# rev0_1.net
KiCad netlist of a schematic drawn in EAGLE
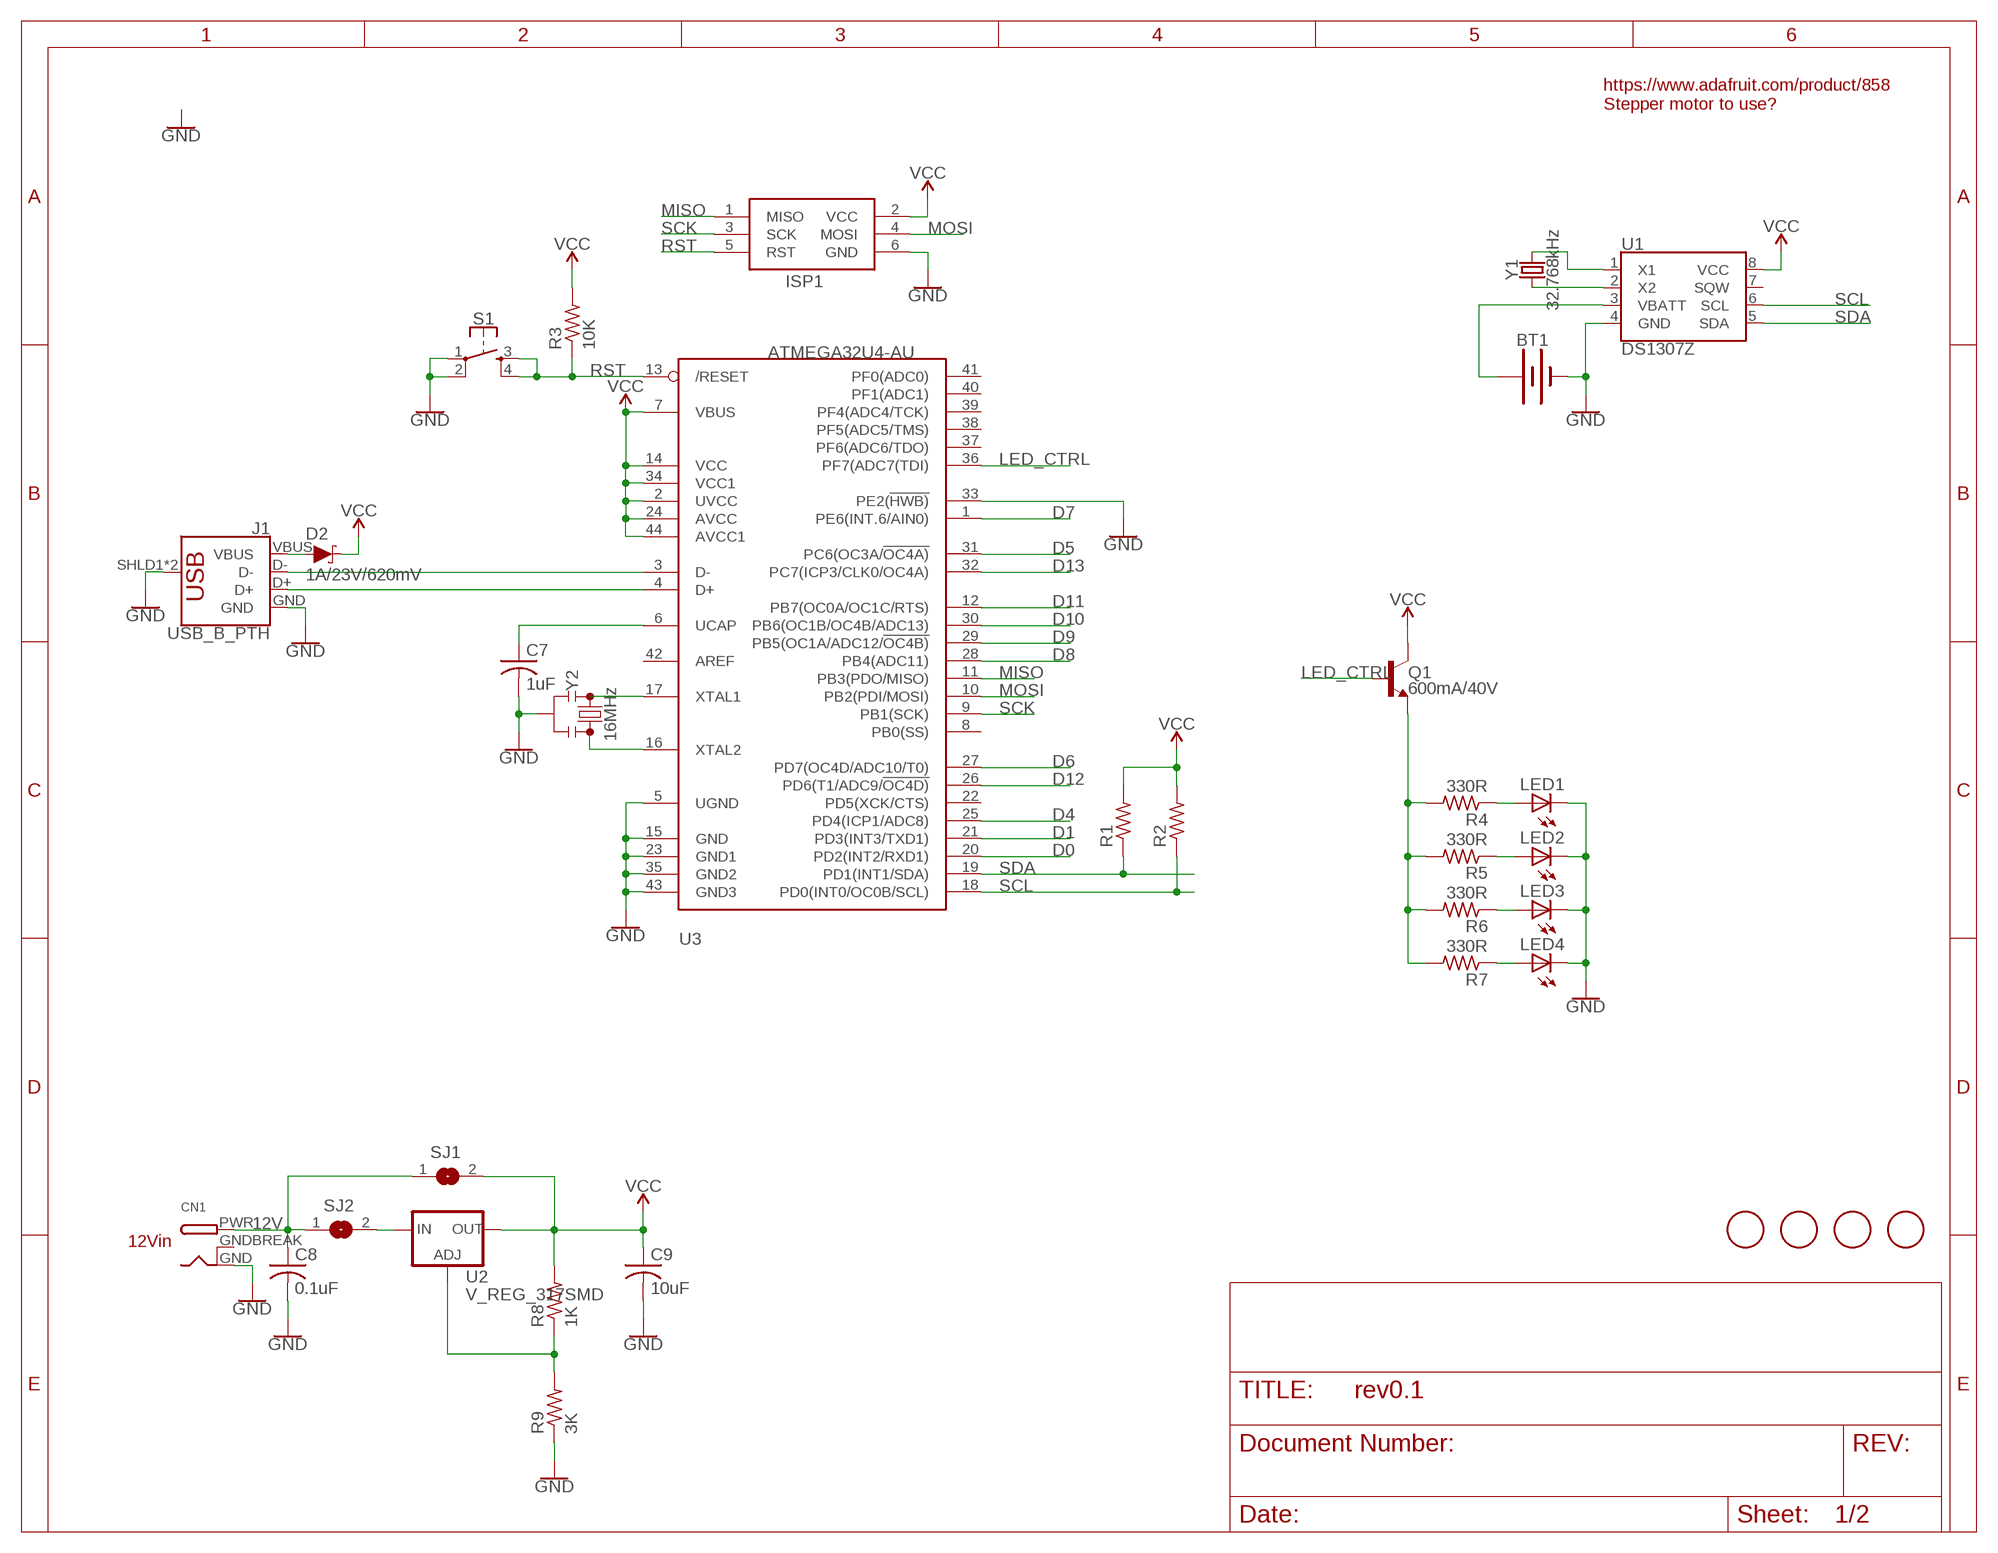
[diagram p0: schematic, sheet 1]
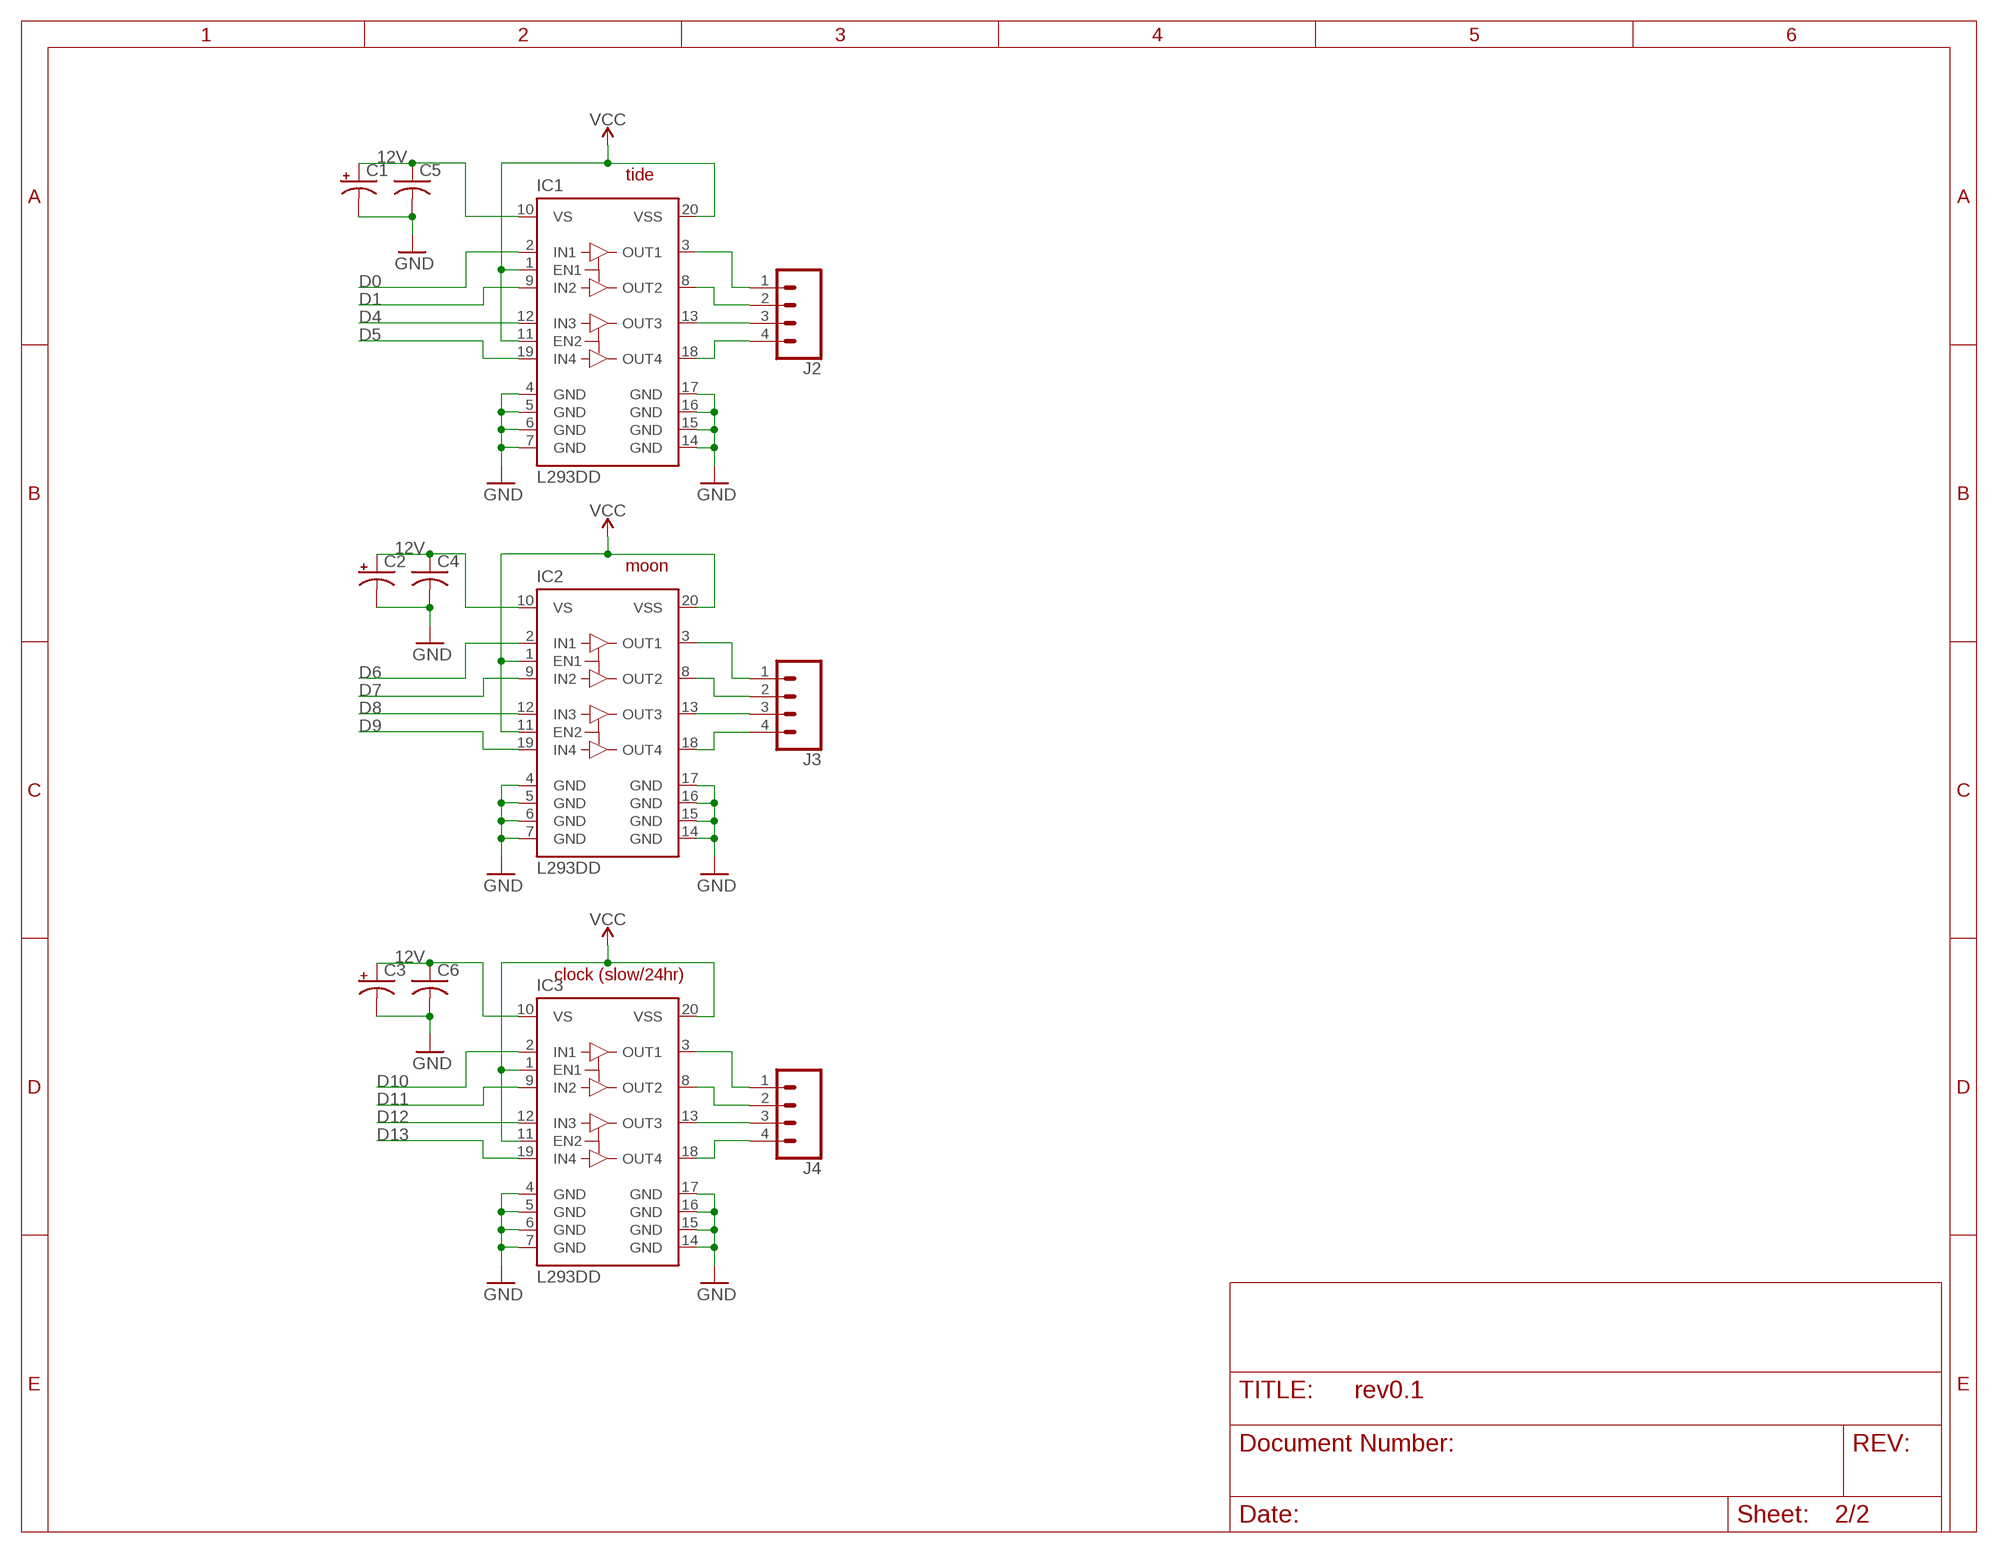
[diagram p1: schematic, sheet 2]

(export (version "E")
  (design (tool "Eeschema 10.0.6"))
  (components
    (comp (ref "C1")
      (value "CPOL-USD")
      (footprint "eagle-import:PANASONIC_D")
      (libsource (lib "eagle-import") (part "CPOL-USD"))
    )
    (comp (ref "C2")
      (value "CPOL-USD")
      (footprint "eagle-import:PANASONIC_D")
      (libsource (lib "eagle-import") (part "CPOL-USD"))
    )
    (comp (ref "C3")
      (value "CPOL-USD")
      (footprint "eagle-import:PANASONIC_D")
      (libsource (lib "eagle-import") (part "CPOL-USD"))
    )
    (comp (ref "C4")
      (value "C-USC0805")
      (footprint "eagle-import:C0805")
      (libsource (lib "eagle-import") (part "C-USC0805"))
    )
    (comp (ref "C5")
      (value "C-USC0805")
      (footprint "eagle-import:C0805")
      (libsource (lib "eagle-import") (part "C-USC0805"))
    )
    (comp (ref "C6")
      (value "C-USC0805")
      (footprint "eagle-import:C0805")
      (libsource (lib "eagle-import") (part "C-USC0805"))
    )
    (comp (ref "IC1")
      (value "L293DD")
      (footprint "eagle-import:SO20")
      (libsource (lib "eagle-import") (part "L293DD"))
    )
    (comp (ref "IC2")
      (value "L293DD")
      (footprint "eagle-import:SO20")
      (libsource (lib "eagle-import") (part "L293DD"))
    )
    (comp (ref "IC3")
      (value "L293DD")
      (footprint "eagle-import:SO20")
      (libsource (lib "eagle-import") (part "L293DD"))
    )
    (comp (ref "J2")
      (value "CONN_04LOCK")
      (footprint "eagle-import:1X04_LOCK")
      (libsource (lib "eagle-import") (part "CONN_04LOCK"))
    )
    (comp (ref "J3")
      (value "CONN_04LOCK")
      (footprint "eagle-import:1X04_LOCK")
      (libsource (lib "eagle-import") (part "CONN_04LOCK"))
    )
    (comp (ref "J4")
      (value "CONN_04LOCK")
      (footprint "eagle-import:1X04_LOCK")
      (libsource (lib "eagle-import") (part "CONN_04LOCK"))
    )
    (comp (ref "BT1")
      (value "BATTERY-12MM_SMD")
      (footprint "eagle-import:BATTCON_12MM")
      (libsource (lib "eagle-import") (part "BATTERY-12MM_SMD"))
    )
    (comp (ref "C7")
      (value "1uF")
      (footprint "eagle-import:C0805")
      (libsource (lib "eagle-import") (part "C-USC0805"))
    )
    (comp (ref "C8")
      (value "0.1uF")
      (footprint "eagle-import:C0805")
      (libsource (lib "eagle-import") (part "C-USC0805"))
    )
    (comp (ref "C9")
      (value "10uF")
      (footprint "eagle-import:C0805")
      (libsource (lib "eagle-import") (part "C-USC0805"))
    )
    (comp (ref "CN1")
      (value "DCBARRELPTH")
      (footprint "eagle-import:DCJACK_2MM_PTH")
      (libsource (lib "eagle-import") (part "DCBARRELPTH"))
    )
    (comp (ref "D2")
      (value "1A/23V/620mV")
      (footprint "eagle-import:SOD-323")
      (libsource (lib "eagle-import") (part "DIODE-SCHOTTKY-BAT20J"))
    )
    (comp (ref "ISP1")
      (value "AVRISP-6")
      (footprint "eagle-import:AVRISP")
      (libsource (lib "eagle-import") (part "AVRISP-6"))
    )
    (comp (ref "J1")
      (value "USB_B_PTH")
      (footprint "eagle-import:USB-B-PTH")
      (libsource (lib "eagle-import") (part "USB_B_PTH"))
    )
    (comp (ref "LED1")
      (value "LEDCHIPLED_0805")
      (footprint "eagle-import:CHIPLED_0805")
      (libsource (lib "eagle-import") (part "LEDCHIPLED_0805"))
    )
    (comp (ref "LED2")
      (value "LEDCHIPLED_0805")
      (footprint "eagle-import:CHIPLED_0805")
      (libsource (lib "eagle-import") (part "LEDCHIPLED_0805"))
    )
    (comp (ref "LED3")
      (value "LEDCHIPLED_0805")
      (footprint "eagle-import:CHIPLED_0805")
      (libsource (lib "eagle-import") (part "LEDCHIPLED_0805"))
    )
    (comp (ref "LED4")
      (value "LEDCHIPLED_0805")
      (footprint "eagle-import:CHIPLED_0805")
      (libsource (lib "eagle-import") (part "LEDCHIPLED_0805"))
    )
    (comp (ref "Q1")
      (value "600mA/40V")
      (footprint "eagle-import:SOT23-3")
      (libsource (lib "eagle-import") (part "TRANS_NPN-MMBT2222AL"))
    )
    (comp (ref "R1")
      (value "R-US_R0805")
      (footprint "eagle-import:R0805")
      (libsource (lib "eagle-import") (part "R-US_R0805"))
    )
    (comp (ref "R2")
      (value "R-US_R0805")
      (footprint "eagle-import:R0805")
      (libsource (lib "eagle-import") (part "R-US_R0805"))
    )
    (comp (ref "R3")
      (value "10K")
      (footprint "eagle-import:R0805")
      (libsource (lib "eagle-import") (part "R-US_R0805"))
    )
    (comp (ref "R4")
      (value "330R")
      (footprint "eagle-import:R0805")
      (libsource (lib "eagle-import") (part "R-US_R0805"))
    )
    (comp (ref "R5")
      (value "330R")
      (footprint "eagle-import:R0805")
      (libsource (lib "eagle-import") (part "R-US_R0805"))
    )
    (comp (ref "R6")
      (value "330R")
      (footprint "eagle-import:R0805")
      (libsource (lib "eagle-import") (part "R-US_R0805"))
    )
    (comp (ref "R7")
      (value "330R")
      (footprint "eagle-import:R0805")
      (libsource (lib "eagle-import") (part "R-US_R0805"))
    )
    (comp (ref "R8")
      (value "1K")
      (footprint "eagle-import:R0805")
      (libsource (lib "eagle-import") (part "R-US_R0805"))
    )
    (comp (ref "R9")
      (value "3K")
      (footprint "eagle-import:R0805")
      (libsource (lib "eagle-import") (part "R-US_R0805"))
    )
    (comp (ref "S1")
      (value "MOMENTARY-SWITCH-SPST-2-SMD-5.2MM")
      (footprint "eagle-import:TACTILE_SWITCH_SMD_5.2MM")
      (libsource (lib "eagle-import") (part "MOMENTARY-SWITCH-SPST-2-SMD-5.2MM"))
    )
    (comp (ref "SJ1") (value "SJ") (footprint "eagle-import:SJ") (libsource (lib "eagle-import") (part "SJ")))
    (comp (ref "SJ2") (value "SJ") (footprint "eagle-import:SJ") (libsource (lib "eagle-import") (part "SJ")))
    (comp (ref "U$2")
      (value "FIDUCIAL")
      (footprint "eagle-import:FIDUCIAL_1MM")
      (libsource (lib "eagle-import") (part "FIDUCIAL"))
    )
    (comp (ref "U$3")
      (value "FIDUCIAL")
      (footprint "eagle-import:FIDUCIAL_1MM")
      (libsource (lib "eagle-import") (part "FIDUCIAL"))
    )
    (comp (ref "U$4")
      (value "FIDUCIAL")
      (footprint "eagle-import:FIDUCIAL_1MM")
      (libsource (lib "eagle-import") (part "FIDUCIAL"))
    )
    (comp (ref "U$5")
      (value "FIDUCIAL")
      (footprint "eagle-import:FIDUCIAL_1MM")
      (libsource (lib "eagle-import") (part "FIDUCIAL"))
    )
    (comp (ref "U1")
      (value "DS1307Z")
      (footprint "eagle-import:SO08-0.15")
      (libsource (lib "eagle-import") (part "DS1307Z"))
    )
    (comp (ref "U2")
      (value "V_REG_317SMD")
      (footprint "eagle-import:SOT223")
      (libsource (lib "eagle-import") (part "V_REG_317SMD"))
    )
    (comp (ref "U3")
      (value "ATMEGA32U4-AU")
      (footprint "eagle-import:TQFP44")
      (libsource (lib "eagle-import") (part "ATMEGA32U4-AU"))
    )
    (comp (ref "Y1")
      (value "32.768kHz")
      (footprint "eagle-import:CRYSTAL-PTH-2X6-CYL-KIT")
      (libsource (lib "eagle-import") (part "CRYSTAL-32.768KHZPTH-2X6-KIT"))
    )
    (comp (ref "Y2")
      (value "16MHz")
      (footprint "eagle-import:RESONATOR-SMD-3.2X1.3")
      (libsource (lib "eagle-import") (part "RESONATOR-16MHZSMD_3.2X1.3"))
    )
  )
  (nets
    (net (code "1") (name "12V") (class "Default")
      (node (ref "C1") (pin "+") (pinfunction "+_+") (pintype "passive"))
      (node (ref "C2") (pin "+") (pinfunction "+_+") (pintype "passive"))
      (node (ref "C3") (pin "+") (pinfunction "+_+") (pintype "passive"))
      (node (ref "C4") (pin "1") (pinfunction "1_1") (pintype "passive"))
      (node (ref "C5") (pin "1") (pinfunction "1_1") (pintype "passive"))
      (node (ref "C6") (pin "1") (pinfunction "1_1") (pintype "passive"))
      (node (ref "C8") (pin "1") (pinfunction "1_1") (pintype "passive"))
      (node (ref "CN1") (pin "PWR") (pinfunction "PWR_PWR") (pintype "power_in"))
      (node (ref "IC1") (pin "10") (pinfunction "VS_10") (pintype "power_in"))
      (node (ref "IC2") (pin "10") (pinfunction "VS_10") (pintype "power_in"))
      (node (ref "IC3") (pin "10") (pinfunction "VS_10") (pintype "power_in"))
      (node (ref "SJ1") (pin "1") (pinfunction "1_1") (pintype "passive"))
      (node (ref "SJ2") (pin "1") (pinfunction "1_1") (pintype "passive"))
    )
    (net (code "2") (name "D0") (class "Default")
      (node (ref "IC1") (pin "2") (pinfunction "IN1_2") (pintype "input"))
      (node (ref "U3") (pin "20") (pinfunction "PD2(INT2/RXD1)_20") (pintype "bidirectional"))
    )
    (net (code "3") (name "D1") (class "Default")
      (node (ref "IC1") (pin "9") (pinfunction "IN2_9") (pintype "input"))
      (node (ref "U3") (pin "21") (pinfunction "PD3(INT3/TXD1)_21") (pintype "bidirectional"))
    )
    (net (code "4") (name "D4") (class "Default")
      (node (ref "IC1") (pin "12") (pinfunction "IN3_12") (pintype "input"))
      (node (ref "U3") (pin "25") (pinfunction "PD4(ICP1/ADC8)_25") (pintype "bidirectional"))
    )
    (net (code "5") (name "D5") (class "Default")
      (node (ref "IC1") (pin "19") (pinfunction "IN4_19") (pintype "input"))
      (node (ref "U3") (pin "31") (pinfunction "PC6(OC3A/~{OC4A})_31") (pintype "bidirectional"))
    )
    (net (code "6") (name "D6") (class "Default")
      (node (ref "IC2") (pin "2") (pinfunction "IN1_2") (pintype "input"))
      (node (ref "U3") (pin "27") (pinfunction "PD7(OC4D/ADC10/T0)_27") (pintype "bidirectional"))
    )
    (net (code "7") (name "D7") (class "Default")
      (node (ref "IC2") (pin "9") (pinfunction "IN2_9") (pintype "input"))
      (node (ref "U3") (pin "1") (pinfunction "PE6(INT.6/AIN0)_1") (pintype "bidirectional"))
    )
    (net (code "8") (name "D8") (class "Default")
      (node (ref "IC2") (pin "12") (pinfunction "IN3_12") (pintype "input"))
      (node (ref "U3") (pin "28") (pinfunction "PB4(ADC11)_28") (pintype "bidirectional"))
    )
    (net (code "9") (name "D9") (class "Default")
      (node (ref "IC2") (pin "19") (pinfunction "IN4_19") (pintype "input"))
      (node (ref "U3") (pin "29") (pinfunction "PB5(OC1A/ADC12/~{OC4B})_29") (pintype "bidirectional"))
    )
    (net (code "10") (name "D10") (class "Default")
      (node (ref "IC3") (pin "2") (pinfunction "IN1_2") (pintype "input"))
      (node (ref "U3") (pin "30") (pinfunction "PB6(OC1B/OC4B/ADC13)_30") (pintype "bidirectional"))
    )
    (net (code "11") (name "D11") (class "Default")
      (node (ref "IC3") (pin "9") (pinfunction "IN2_9") (pintype "input"))
      (node (ref "U3") (pin "12") (pinfunction "PB7(OC0A/OC1C/RTS)_12") (pintype "bidirectional"))
    )
    (net (code "12") (name "D12") (class "Default")
      (node (ref "IC3") (pin "12") (pinfunction "IN3_12") (pintype "input"))
      (node (ref "U3") (pin "26") (pinfunction "PD6(T1/ADC9/~{OC4D})_26") (pintype "bidirectional"))
    )
    (net (code "13") (name "D13") (class "Default")
      (node (ref "IC3") (pin "19") (pinfunction "IN4_19") (pintype "input"))
      (node (ref "U3") (pin "32") (pinfunction "PC7(ICP3/CLK0/OC4A)_32") (pintype "bidirectional"))
    )
    (net (code "14") (name "GND") (class "Default")
      (node (ref "BT1") (pin "GND") (pinfunction "-_GND") (pintype "power_in"))
      (node (ref "C1") (pin "-") (pinfunction "-_-") (pintype "passive"))
      (node (ref "C2") (pin "-") (pinfunction "-_-") (pintype "passive"))
      (node (ref "C3") (pin "-") (pinfunction "-_-") (pintype "passive"))
      (node (ref "C4") (pin "2") (pinfunction "2_2") (pintype "passive"))
      (node (ref "C5") (pin "2") (pinfunction "2_2") (pintype "passive"))
      (node (ref "C6") (pin "2") (pinfunction "2_2") (pintype "passive"))
      (node (ref "C7") (pin "2") (pinfunction "2_2") (pintype "passive"))
      (node (ref "C8") (pin "2") (pinfunction "2_2") (pintype "passive"))
      (node (ref "C9") (pin "2") (pinfunction "2_2") (pintype "passive"))
      (node (ref "CN1") (pin "GND") (pinfunction "GND_GND") (pintype "power_in"))
      (node (ref "IC1") (pin "14") (pinfunction "GND_14") (pintype "power_in"))
      (node (ref "IC1") (pin "15") (pinfunction "GND_15") (pintype "power_in"))
      (node (ref "IC1") (pin "16") (pinfunction "GND_16") (pintype "power_in"))
      (node (ref "IC1") (pin "17") (pinfunction "GND_17") (pintype "power_in"))
      (node (ref "IC1") (pin "4") (pinfunction "GND_4") (pintype "power_in"))
      (node (ref "IC1") (pin "5") (pinfunction "GND_5") (pintype "power_in"))
      (node (ref "IC1") (pin "6") (pinfunction "GND_6") (pintype "power_in"))
      (node (ref "IC1") (pin "7") (pinfunction "GND_7") (pintype "power_in"))
      (node (ref "IC2") (pin "14") (pinfunction "GND_14") (pintype "power_in"))
      (node (ref "IC2") (pin "15") (pinfunction "GND_15") (pintype "power_in"))
      (node (ref "IC2") (pin "16") (pinfunction "GND_16") (pintype "power_in"))
      (node (ref "IC2") (pin "17") (pinfunction "GND_17") (pintype "power_in"))
      (node (ref "IC2") (pin "4") (pinfunction "GND_4") (pintype "power_in"))
      (node (ref "IC2") (pin "5") (pinfunction "GND_5") (pintype "power_in"))
      (node (ref "IC2") (pin "6") (pinfunction "GND_6") (pintype "power_in"))
      (node (ref "IC2") (pin "7") (pinfunction "GND_7") (pintype "power_in"))
      (node (ref "IC3") (pin "14") (pinfunction "GND_14") (pintype "power_in"))
      (node (ref "IC3") (pin "15") (pinfunction "GND_15") (pintype "power_in"))
      (node (ref "IC3") (pin "16") (pinfunction "GND_16") (pintype "power_in"))
      (node (ref "IC3") (pin "17") (pinfunction "GND_17") (pintype "power_in"))
      (node (ref "IC3") (pin "4") (pinfunction "GND_4") (pintype "power_in"))
      (node (ref "IC3") (pin "5") (pinfunction "GND_5") (pintype "power_in"))
      (node (ref "IC3") (pin "6") (pinfunction "GND_6") (pintype "power_in"))
      (node (ref "IC3") (pin "7") (pinfunction "GND_7") (pintype "power_in"))
      (node (ref "ISP1") (pin "6") (pinfunction "GND_6") (pintype "power_in"))
      (node (ref "J1") (pin "GND") (pinfunction "GND_GND") (pintype "power_in"))
      (node (ref "J1") (pin "SHLD1") (pinfunction "SHIELD_SHLD1") (pintype "bidirectional"))
      (node (ref "J1") (pin "SHLD2") (pinfunction "SHIELD_SHLD2") (pintype "bidirectional"))
      (node (ref "LED1") (pin "C") (pinfunction "C_C") (pintype "passive"))
      (node (ref "LED2") (pin "C") (pinfunction "C_C") (pintype "passive"))
      (node (ref "LED3") (pin "C") (pinfunction "C_C") (pintype "passive"))
      (node (ref "LED4") (pin "C") (pinfunction "C_C") (pintype "passive"))
      (node (ref "R9") (pin "1") (pinfunction "1_1") (pintype "passive"))
      (node (ref "S1") (pin "1") (pinfunction "1_1") (pintype "passive"))
      (node (ref "S1") (pin "2") (pinfunction "2_2") (pintype "passive"))
      (node (ref "U1") (pin "4") (pinfunction "GND_4") (pintype "bidirectional"))
      (node (ref "U3") (pin "15") (pinfunction "GND_15") (pintype "bidirectional"))
      (node (ref "U3") (pin "23") (pinfunction "GND1_23") (pintype "bidirectional"))
      (node (ref "U3") (pin "33") (pinfunction "PE2(~{HWB})_33") (pintype "bidirectional"))
      (node (ref "U3") (pin "35") (pinfunction "GND2_35") (pintype "bidirectional"))
      (node (ref "U3") (pin "43") (pinfunction "GND3_43") (pintype "bidirectional"))
      (node (ref "U3") (pin "5") (pinfunction "UGND_5") (pintype "bidirectional"))
      (node (ref "Y2") (pin "2") (pinfunction "2_2") (pintype "passive"))
    )
    (net (code "15") (name "GNDBREAK") (class "Default")
      (node (ref "CN1") (pin "GNDBREAK") (pinfunction "GNDBREAK_GNDBREAK") (pintype "power_in"))
    )
    (net (code "16") (name "LED_CTRL") (class "Default")
      (node (ref "Q1") (pin "1") (pinfunction "B_1") (pintype "passive"))
      (node (ref "U3") (pin "36") (pinfunction "PF7(ADC7(TDI)_36") (pintype "bidirectional"))
    )
    (net (code "17") (name "MISO") (class "Default")
      (node (ref "ISP1") (pin "1") (pinfunction "MISO_1") (pintype "input"))
      (node (ref "U3") (pin "11") (pinfunction "PB3(PDO/MISO)_11") (pintype "bidirectional"))
    )
    (net (code "18") (name "MOSI") (class "Default")
      (node (ref "ISP1") (pin "4") (pinfunction "MOSI_4") (pintype "output"))
      (node (ref "U3") (pin "10") (pinfunction "PB2(PDI/MOSI)_10") (pintype "bidirectional"))
    )
    (net (code "19") (name "Net-(BT1-+)") (class "Default")
      (node (ref "BT1") (pin "PWR@1") (pinfunction "+_PWR@1") (pintype "power_in"))
      (node (ref "U1") (pin "3") (pinfunction "VBATT_3") (pintype "bidirectional"))
    )
    (net (code "20") (name "Net-(D2-PadA)") (class "Default")
      (node (ref "D2") (pin "A") (pinfunction "A_A") (pintype "passive"))
      (node (ref "J1") (pin "VBUS") (pinfunction "VBUS_VBUS") (pintype "power_in"))
    )
    (net (code "21") (name "Net-(IC1-OUT1)") (class "Default")
      (node (ref "IC1") (pin "3") (pinfunction "OUT1_3") (pintype "output"))
      (node (ref "J2") (pin "1") (pinfunction "1_1") (pintype "passive"))
    )
    (net (code "22") (name "Net-(IC1-OUT2)") (class "Default")
      (node (ref "IC1") (pin "8") (pinfunction "OUT2_8") (pintype "output"))
      (node (ref "J2") (pin "2") (pinfunction "2_2") (pintype "passive"))
    )
    (net (code "23") (name "Net-(IC1-OUT3)") (class "Default")
      (node (ref "IC1") (pin "13") (pinfunction "OUT3_13") (pintype "output"))
      (node (ref "J2") (pin "3") (pinfunction "3_3") (pintype "passive"))
    )
    (net (code "24") (name "Net-(IC1-OUT4)") (class "Default")
      (node (ref "IC1") (pin "18") (pinfunction "OUT4_18") (pintype "output"))
      (node (ref "J2") (pin "4") (pinfunction "4_4") (pintype "passive"))
    )
    (net (code "25") (name "Net-(IC2-OUT1)") (class "Default")
      (node (ref "IC2") (pin "3") (pinfunction "OUT1_3") (pintype "output"))
      (node (ref "J3") (pin "1") (pinfunction "1_1") (pintype "passive"))
    )
    (net (code "26") (name "Net-(IC2-OUT2)") (class "Default")
      (node (ref "IC2") (pin "8") (pinfunction "OUT2_8") (pintype "output"))
      (node (ref "J3") (pin "2") (pinfunction "2_2") (pintype "passive"))
    )
    (net (code "27") (name "Net-(IC2-OUT3)") (class "Default")
      (node (ref "IC2") (pin "13") (pinfunction "OUT3_13") (pintype "output"))
      (node (ref "J3") (pin "3") (pinfunction "3_3") (pintype "passive"))
    )
    (net (code "28") (name "Net-(IC2-OUT4)") (class "Default")
      (node (ref "IC2") (pin "18") (pinfunction "OUT4_18") (pintype "output"))
      (node (ref "J3") (pin "4") (pinfunction "4_4") (pintype "passive"))
    )
    (net (code "29") (name "Net-(IC3-OUT1)") (class "Default")
      (node (ref "IC3") (pin "3") (pinfunction "OUT1_3") (pintype "output"))
      (node (ref "J4") (pin "1") (pinfunction "1_1") (pintype "passive"))
    )
    (net (code "30") (name "Net-(IC3-OUT2)") (class "Default")
      (node (ref "IC3") (pin "8") (pinfunction "OUT2_8") (pintype "output"))
      (node (ref "J4") (pin "2") (pinfunction "2_2") (pintype "passive"))
    )
    (net (code "31") (name "Net-(IC3-OUT3)") (class "Default")
      (node (ref "IC3") (pin "13") (pinfunction "OUT3_13") (pintype "output"))
      (node (ref "J4") (pin "3") (pinfunction "3_3") (pintype "passive"))
    )
    (net (code "32") (name "Net-(IC3-OUT4)") (class "Default")
      (node (ref "IC3") (pin "18") (pinfunction "OUT4_18") (pintype "output"))
      (node (ref "J4") (pin "4") (pinfunction "4_4") (pintype "passive"))
    )
    (net (code "33") (name "Net-(LED1-PadA)") (class "Default")
      (node (ref "LED1") (pin "A") (pinfunction "A_A") (pintype "passive"))
      (node (ref "R4") (pin "1") (pinfunction "1_1") (pintype "passive"))
    )
    (net (code "34") (name "Net-(LED2-PadA)") (class "Default")
      (node (ref "LED2") (pin "A") (pinfunction "A_A") (pintype "passive"))
      (node (ref "R5") (pin "1") (pinfunction "1_1") (pintype "passive"))
    )
    (net (code "35") (name "Net-(LED3-PadA)") (class "Default")
      (node (ref "LED3") (pin "A") (pinfunction "A_A") (pintype "passive"))
      (node (ref "R6") (pin "1") (pinfunction "1_1") (pintype "passive"))
    )
    (net (code "36") (name "Net-(LED4-PadA)") (class "Default")
      (node (ref "LED4") (pin "A") (pinfunction "A_A") (pintype "passive"))
      (node (ref "R7") (pin "1") (pinfunction "1_1") (pintype "passive"))
    )
    (net (code "37") (name "Net-(Q1-E)") (class "Default")
      (node (ref "Q1") (pin "2") (pinfunction "E_2") (pintype "passive"))
      (node (ref "R4") (pin "2") (pinfunction "2_2") (pintype "passive"))
      (node (ref "R5") (pin "2") (pinfunction "2_2") (pintype "passive"))
      (node (ref "R6") (pin "2") (pinfunction "2_2") (pintype "passive"))
      (node (ref "R7") (pin "2") (pinfunction "2_2") (pintype "passive"))
    )
    (net (code "38") (name "Net-(U1-X1)") (class "Default")
      (node (ref "U1") (pin "1") (pinfunction "X1_1") (pintype "bidirectional"))
      (node (ref "Y1") (pin "2") (pinfunction "2_2") (pintype "passive"))
    )
    (net (code "39") (name "Net-(U1-X2)") (class "Default")
      (node (ref "U1") (pin "2") (pinfunction "X2_2") (pintype "bidirectional"))
      (node (ref "Y1") (pin "1") (pinfunction "1_1") (pintype "passive"))
    )
    (net (code "40") (name "Net-(U2-ADJ)") (class "Default")
      (node (ref "R8") (pin "1") (pinfunction "1_1") (pintype "passive"))
      (node (ref "R9") (pin "2") (pinfunction "2_2") (pintype "passive"))
      (node (ref "U2") (pin "1") (pinfunction "ADJ_1") (pintype "input"))
    )
    (net (code "41") (name "Net-(U2-IN)") (class "Default")
      (node (ref "SJ2") (pin "2") (pinfunction "2_2") (pintype "passive"))
      (node (ref "U2") (pin "3") (pinfunction "IN_3") (pintype "input"))
    )
    (net (code "42") (name "Net-(U3-D+)") (class "Default")
      (node (ref "J1") (pin "D+") (pinfunction "D+_D+") (pintype "bidirectional"))
      (node (ref "U3") (pin "4") (pinfunction "D+_4") (pintype "bidirectional"))
    )
    (net (code "43") (name "Net-(U3-D-)") (class "Default")
      (node (ref "J1") (pin "D-") (pinfunction "D-_D-") (pintype "bidirectional"))
      (node (ref "U3") (pin "3") (pinfunction "D-_3") (pintype "bidirectional"))
    )
    (net (code "44") (name "Net-(U3-UCAP)") (class "Default")
      (node (ref "C7") (pin "1") (pinfunction "1_1") (pintype "passive"))
      (node (ref "U3") (pin "6") (pinfunction "UCAP_6") (pintype "bidirectional"))
    )
    (net (code "45") (name "Net-(U3-XTAL1)") (class "Default")
      (node (ref "U3") (pin "17") (pinfunction "XTAL1_17") (pintype "bidirectional"))
      (node (ref "Y2") (pin "1") (pinfunction "1_1") (pintype "passive"))
    )
    (net (code "46") (name "Net-(U3-XTAL2)") (class "Default")
      (node (ref "U3") (pin "16") (pinfunction "XTAL2_16") (pintype "bidirectional"))
      (node (ref "Y2") (pin "3") (pinfunction "3_3") (pintype "passive"))
    )
    (net (code "47") (name "RST") (class "Default")
      (node (ref "ISP1") (pin "5") (pinfunction "RST_5") (pintype "output"))
      (node (ref "R3") (pin "1") (pinfunction "1_1") (pintype "passive"))
      (node (ref "S1") (pin "3") (pinfunction "3_3") (pintype "passive"))
      (node (ref "S1") (pin "4") (pinfunction "4_4") (pintype "passive"))
      (node (ref "U3") (pin "13") (pinfunction "/RESET_13") (pintype "bidirectional"))
    )
    (net (code "48") (name "SCK") (class "Default")
      (node (ref "ISP1") (pin "3") (pinfunction "SCK_3") (pintype "output"))
      (node (ref "U3") (pin "9") (pinfunction "PB1(SCK)_9") (pintype "bidirectional"))
    )
    (net (code "49") (name "SCL") (class "Default")
      (node (ref "R2") (pin "1") (pinfunction "1_1") (pintype "passive"))
      (node (ref "U1") (pin "6") (pinfunction "SCL_6") (pintype "bidirectional"))
      (node (ref "U3") (pin "18") (pinfunction "PD0(INT0/OC0B/SCL)_18") (pintype "bidirectional"))
    )
    (net (code "50") (name "SDA") (class "Default")
      (node (ref "R1") (pin "1") (pinfunction "1_1") (pintype "passive"))
      (node (ref "U1") (pin "5") (pinfunction "SDA_5") (pintype "bidirectional"))
      (node (ref "U3") (pin "19") (pinfunction "PD1(INT1/SDA)_19") (pintype "bidirectional"))
    )
    (net (code "51") (name "VCC") (class "Default")
      (node (ref "C9") (pin "1") (pinfunction "1_1") (pintype "passive"))
      (node (ref "D2") (pin "C") (pinfunction "C_C") (pintype "passive"))
      (node (ref "IC1") (pin "1") (pinfunction "EN1_1") (pintype "input"))
      (node (ref "IC1") (pin "11") (pinfunction "EN2_11") (pintype "input"))
      (node (ref "IC1") (pin "20") (pinfunction "VSS_20") (pintype "power_in"))
      (node (ref "IC2") (pin "1") (pinfunction "EN1_1") (pintype "input"))
      (node (ref "IC2") (pin "11") (pinfunction "EN2_11") (pintype "input"))
      (node (ref "IC2") (pin "20") (pinfunction "VSS_20") (pintype "power_in"))
      (node (ref "IC3") (pin "1") (pinfunction "EN1_1") (pintype "input"))
      (node (ref "IC3") (pin "11") (pinfunction "EN2_11") (pintype "input"))
      (node (ref "IC3") (pin "20") (pinfunction "VSS_20") (pintype "power_in"))
      (node (ref "ISP1") (pin "2") (pinfunction "VCC_2") (pintype "power_in"))
      (node (ref "Q1") (pin "3") (pinfunction "C_3") (pintype "passive"))
      (node (ref "R1") (pin "2") (pinfunction "2_2") (pintype "passive"))
      (node (ref "R2") (pin "2") (pinfunction "2_2") (pintype "passive"))
      (node (ref "R3") (pin "2") (pinfunction "2_2") (pintype "passive"))
      (node (ref "R8") (pin "2") (pinfunction "2_2") (pintype "passive"))
      (node (ref "SJ1") (pin "2") (pinfunction "2_2") (pintype "passive"))
      (node (ref "U1") (pin "8") (pinfunction "VCC_8") (pintype "bidirectional"))
      (node (ref "U2") (pin "2") (pinfunction "OUT_2") (pintype "output"))
      (node (ref "U3") (pin "14") (pinfunction "VCC_14") (pintype "bidirectional"))
      (node (ref "U3") (pin "2") (pinfunction "UVCC_2") (pintype "bidirectional"))
      (node (ref "U3") (pin "24") (pinfunction "AVCC_24") (pintype "bidirectional"))
      (node (ref "U3") (pin "34") (pinfunction "VCC1_34") (pintype "bidirectional"))
      (node (ref "U3") (pin "44") (pinfunction "AVCC1_44") (pintype "bidirectional"))
      (node (ref "U3") (pin "7") (pinfunction "VBUS_7") (pintype "bidirectional"))
    )
    (net (code "52") (name "unconnected-(U1-SQW-Pad7)") (class "Default")
      (node (ref "U1") (pin "7") (pinfunction "SQW_7") (pintype "bidirectional"))
    )
    (net (code "53") (name "unconnected-(U3-AREF-Pad42)") (class "Default")
      (node (ref "U3") (pin "42") (pinfunction "AREF_42") (pintype "bidirectional"))
    )
    (net (code "54") (name "unconnected-(U3-PB0(SS)-Pad8)") (class "Default")
      (node (ref "U3") (pin "8") (pinfunction "PB0(SS)_8") (pintype "bidirectional"))
    )
    (net (code "55") (name "unconnected-(U3-PD5(XCK{slash}CTS)-Pad22)") (class "Default")
      (node (ref "U3") (pin "22") (pinfunction "PD5(XCK/CTS)_22") (pintype "bidirectional"))
    )
    (net (code "56") (name "unconnected-(U3-PF0(ADC0)-Pad41)") (class "Default")
      (node (ref "U3") (pin "41") (pinfunction "PF0(ADC0)_41") (pintype "bidirectional"))
    )
    (net (code "57") (name "unconnected-(U3-PF1(ADC1)-Pad40)") (class "Default")
      (node (ref "U3") (pin "40") (pinfunction "PF1(ADC1)_40") (pintype "bidirectional"))
    )
    (net (code "58") (name "unconnected-(U3-PF4(ADC4{slash}TCK)-Pad39)") (class "Default")
      (node (ref "U3") (pin "39") (pinfunction "PF4(ADC4/TCK)_39") (pintype "bidirectional"))
    )
    (net (code "59") (name "unconnected-(U3-PF5(ADC5{slash}TMS)-Pad38)") (class "Default")
      (node (ref "U3") (pin "38") (pinfunction "PF5(ADC5/TMS)_38") (pintype "bidirectional"))
    )
    (net (code "60") (name "unconnected-(U3-PF6(ADC6{slash}TDO)-Pad37)") (class "Default")
      (node (ref "U3") (pin "37") (pinfunction "PF6(ADC6/TDO)_37") (pintype "bidirectional"))
    )
  )
)
